# Power_VCC1V0.net
KiCad netlist of a schematic drawn in Altium Designer
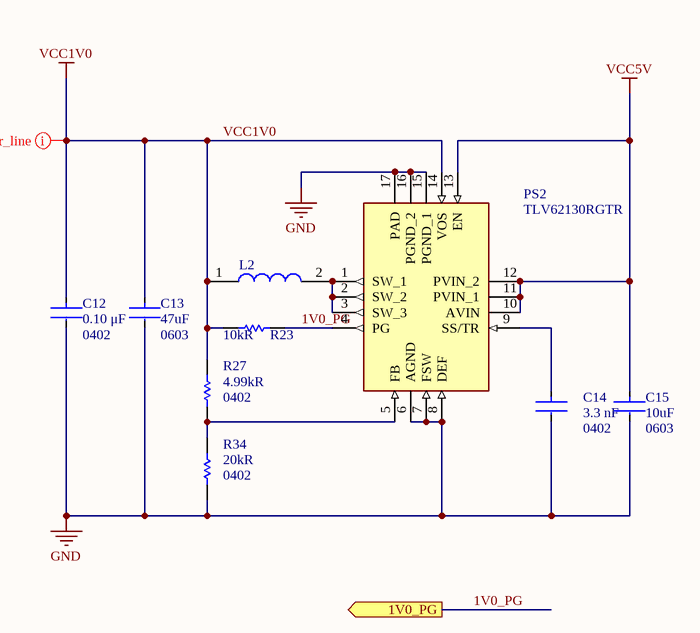
[diagram p0: Power_VCC1V0.SchDoc]

(export (version "E")
  (design (tool "Eeschema 10.0.6"))
  (components
    (comp (ref "C12")
      (value "0.10 μF")
      (footprint "FP-C0402-BB-MFG")
      (description "CAP CER 0.1UF 10V X5R 0402")
      (fields
        (field (name "MANUFACTURER") "Kemet")
        (field (name "TOLERANCE") "0.1")
        (field (name "CASE/PACKAGE") "0402")
      )
      (libsource (lib "Altium Content Vault") (part "b4654b650e69147ec39a6b967a45e02"))
    )
    (comp (ref "C13")
      (value "47uF")
      (footprint "FP-GRM188-0_2-IPC_B")
      (description "Chip Multilayer Ceramic Capacitors for General Purpose, 0603, 47uF, X5R, 15%, 20%, 6.3V")
      (fields
        (field (name "CASE CODE (IMPERIAL)") "0603")
        (field (name "TOLERANCE") "20%")
        (field (name "MANUFACTURER") "Murata")
      )
      (libsource (lib "Altium Content Vault") (part "11868f565c42a9108669ba33697ecf6"))
    )
    (comp (ref "C14")
      (value "3.3 nF")
      (footprint "FP-CC0402-MFG")
      (description "CAP CER 3300PF 50V X7R 0402")
      (fields
        (field (name "OCTOPART") "https://octopart.com/cc0402krx7r9bb332-yageo-192887")
        (field (name "MANUFACTURER") "YAGEO")
        (field (name "CASE/PACKAGE") "0402")
      )
      (libsource (lib "Altium Content Vault") (part "11868f565c42a9108669ba33697ecf6"))
    )
    (comp (ref "C15")
      (value "10uF")
      (footprint "FP-GRM188-0_1-e0_2_0_55-IPC_A")
      (description "Chip Multilayer Ceramic Capacitors for General Purpose, 0603, 10uF, X5R, 15%, 20%, 6.3V")
      (fields
        (field (name "CASE/PACKAGE") "0603")
        (field (name "VOLTAGE") "6.3V")
        (field (name "TOLERANCE") "20%")
      )
      (libsource (lib "Altium Content Vault") (part "02cd4be3c70576c341d710602a673aa"))
    )
    (comp (ref "L2")
      (value "252012CDMCDS2R2MC")
      (footprint "INDPM2520X120N")
      (description "Inductor")
      (fields (field (name "MANUFACTURER_PART_NUMBER") "252012CDMCDS‐2R2MC"))
      (libsource (lib "CCZynq") (part "252012CDMCDS2R2MC"))
    )
    (comp (ref "PS2")
      (value "TLV62130RGTR")
      (footprint "FP-RGT0016C-MFG")
      (description "Buck Switching Regulator IC Positive Adjustable 0.9V 1 Output 3A 16-VFQFN Exposed Pad")
      (fields
        (field (name "MOUSER PART NUMBER") "595-TLV62130RGTR")
        (field (name "MANUFACTURER") "Texas Instruments")
      )
      (libsource (lib "HamedLib") (part "TLV62130RGTR"))
    )
    (comp (ref "R23")
      (value "10kR")
      (footprint "RESC1005X40X25LL05T10")
      (description "10K 0402 1% 1/16W +-100PPM")
      (fields (field (name "PART NUMBER") "RC0402FR-0710KL") (field (name "MANUFACTURER") "Yageo / Phycomp"))
      (libsource (lib "Altium Content Vault") (part "RES"))
    )
    (comp (ref "R27")
      (value "4.99kR")
      (footprint "RESC1005X40X25LL05T10")
      (description "10K 0402 1% 1/16W +-100PPM")
      (fields
        (field (name "MANUFACTURER") "Yageo / Phycomp")
        (field (name "PART NUMBER") "RC0402FR-074K99L")
        (field (name "CASE/PACKAGE") "0402")
      )
      (libsource (lib "Altium Content Vault") (part "RES"))
    )
    (comp (ref "R34")
      (value "20kR")
      (footprint "RESC1005X40X25NL05T10")
      (fields
        (field (name "PART NUMBER") "RC0402FR-0720KL")
        (field (name "MANUFACTURER") "Yageo / Phycomp")
        (field (name "CASE/PACKAGE") "0402")
        (field (name "TOLERANCE") "1%")
      )
      (libsource (lib "Altium Content Vault") (part "RES"))
    )
  )
  (nets
    (net (code "1") (name "/1V0_PG") (class "Default")
      (node (ref "PS2") (pin "4") (pinfunction "PG_4") (pintype "output"))
      (node (ref "R23") (pin "2") (pinfunction "2_2") (pintype "passive"))
    )
    (net (code "2") (name "GND") (class "Default")
      (node (ref "C12") (pin "2") (pinfunction "2_2") (pintype "passive"))
      (node (ref "C13") (pin "2") (pinfunction "2_2") (pintype "passive"))
      (node (ref "C14") (pin "2") (pinfunction "2_2") (pintype "passive"))
      (node (ref "C15") (pin "2") (pinfunction "2_2") (pintype "passive"))
      (node (ref "PS2") (pin "15") (pinfunction "PGND_1_15") (pintype "power_in"))
      (node (ref "PS2") (pin "16") (pinfunction "PGND_2_16") (pintype "power_in"))
      (node (ref "PS2") (pin "17") (pinfunction "PAD_17") (pintype "power_in"))
      (node (ref "PS2") (pin "6") (pinfunction "AGND_6") (pintype "power_in"))
      (node (ref "PS2") (pin "7") (pinfunction "FSW_7") (pintype "input"))
      (node (ref "PS2") (pin "8") (pinfunction "DEF_8") (pintype "input"))
      (node (ref "R34") (pin "1") (pinfunction "1_1") (pintype "passive"))
    )
    (net (code "3") (name "Net-(PS2-FB)") (class "Default")
      (node (ref "PS2") (pin "5") (pinfunction "FB_5") (pintype "input"))
      (node (ref "R27") (pin "1") (pinfunction "1_1") (pintype "passive"))
      (node (ref "R34") (pin "2") (pinfunction "2_2") (pintype "passive"))
    )
    (net (code "4") (name "Net-(PS2-SS{slash}TR)") (class "Default")
      (node (ref "C14") (pin "1") (pinfunction "1_1") (pintype "passive"))
      (node (ref "PS2") (pin "9") (pinfunction "SS/TR_9") (pintype "input"))
    )
    (net (code "5") (name "Net-(PS2-SW_1)") (class "Default")
      (node (ref "L2") (pin "2") (pinfunction "2_2") (pintype "passive"))
      (node (ref "PS2") (pin "1") (pinfunction "SW_1_1") (pintype "output"))
      (node (ref "PS2") (pin "2") (pinfunction "SW_2_2") (pintype "output"))
      (node (ref "PS2") (pin "3") (pinfunction "SW_3_3") (pintype "output"))
    )
    (net (code "6") (name "VCC1V0") (class "Default")
      (node (ref "C12") (pin "1") (pinfunction "1_1") (pintype "passive"))
      (node (ref "C13") (pin "1") (pinfunction "1_1") (pintype "passive"))
      (node (ref "L2") (pin "1") (pinfunction "1_1") (pintype "passive"))
      (node (ref "PS2") (pin "14") (pinfunction "VOS_14") (pintype "input"))
      (node (ref "R23") (pin "1") (pinfunction "1_1") (pintype "passive"))
      (node (ref "R27") (pin "2") (pinfunction "2_2") (pintype "passive"))
    )
    (net (code "7") (name "VCC5V") (class "Default")
      (node (ref "C15") (pin "1") (pinfunction "1_1") (pintype "passive"))
      (node (ref "PS2") (pin "10") (pinfunction "AVIN_10") (pintype "power_in"))
      (node (ref "PS2") (pin "11") (pinfunction "PVIN_1_11") (pintype "power_in"))
      (node (ref "PS2") (pin "12") (pinfunction "PVIN_2_12") (pintype "power_in"))
      (node (ref "PS2") (pin "13") (pinfunction "EN_13") (pintype "input"))
    )
  )
)
